# ProPrj__B__2024-10-31.net
KiCad netlist of a schematic drawn in EasyEDA Pro
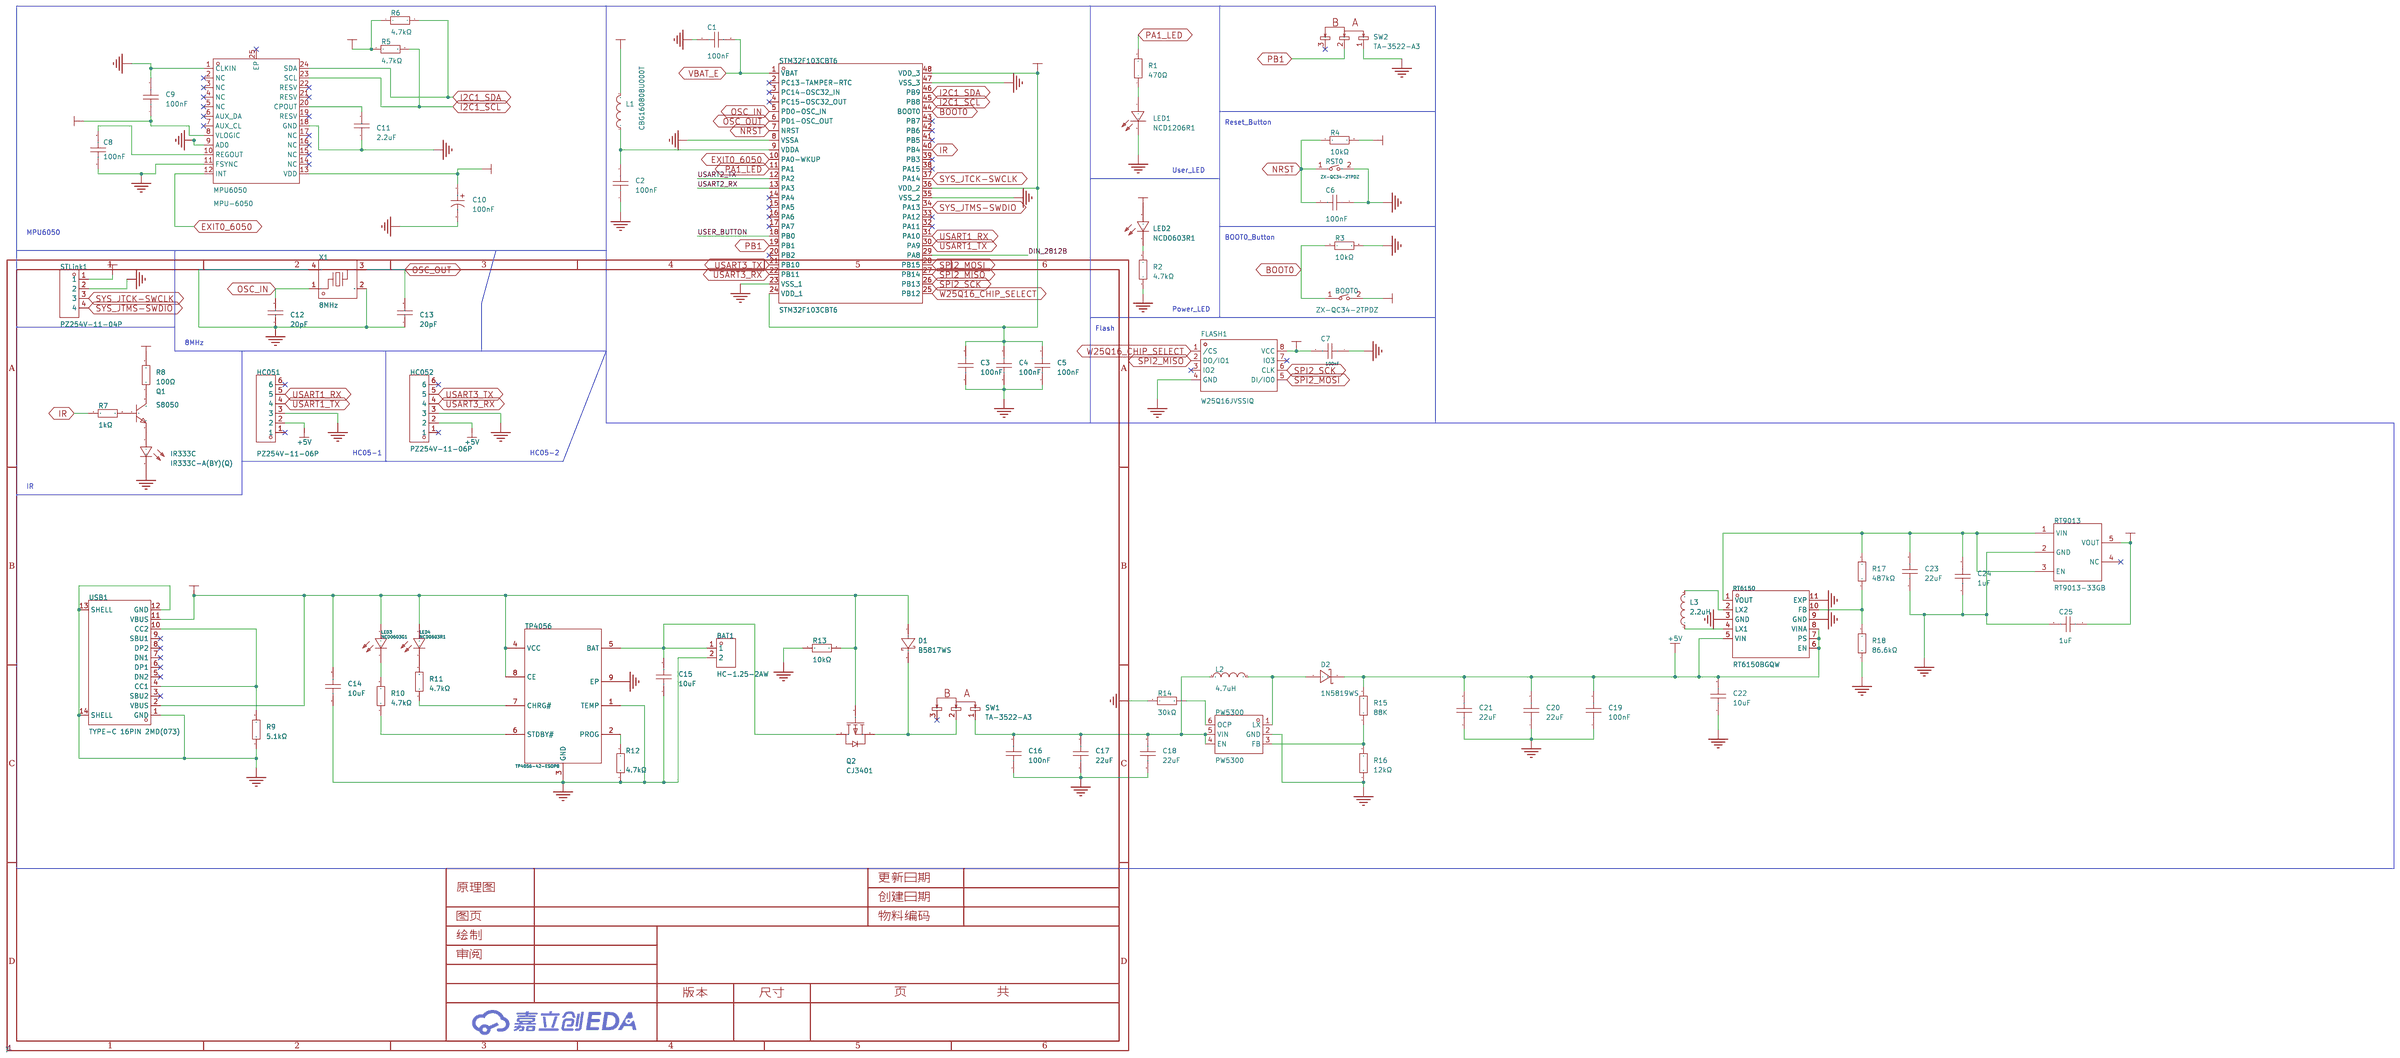
[diagram p0: schematic sheet]

(export (version "E")
  (design (tool "Eeschema 10.0.6"))
  (components
    (comp (ref "BAT1")
      (value "HC-1.25-2AW")
      (footprint "easyedapro:CONN-TH_2P-P1.25_HCTL_HC-1.25-2AW")
      (fields (field (name "Manufacturer") "HCTL(华灿天禄)"))
      (libsource (lib "easyedapro") (part "HC-1.25-2AW"))
    )
    (comp (ref "BOOT0")
      (value "ZX-QC34-2TPDZ")
      (footprint "easyedapro:KEY-SMD_L3.9-W3.0-LS5.0-EH")
      (fields (field (name "Manufacturer") "Megastar(兆星)"))
      (libsource (lib "easyedapro") (part "ZX-QC34-2TPDZ"))
    )
    (comp (ref "C1")
      (value "100nF")
      (footprint "easyedapro:C0603")
      (description "容值:100nF;精度:±10%;额定电压:50V;材质(温度系数):X7R;")
      (fields
        (field (name "Manufacturer Part") "CC0603KRX7R9BB104")
        (field (name "Manufacturer") "YAGEO(国巨)")
      )
      (libsource (lib "easyedapro") (part "CC0603KRX7R9BB104"))
    )
    (comp (ref "C2")
      (value "100nF")
      (footprint "easyedapro:C0603")
      (description "容值:100nF;精度:±10%;额定电压:50V;材质(温度系数):X7R;")
      (fields
        (field (name "Manufacturer Part") "CC0603KRX7R9BB104")
        (field (name "Manufacturer") "YAGEO(国巨)")
      )
      (libsource (lib "easyedapro") (part "CC0603KRX7R9BB104"))
    )
    (comp (ref "C3")
      (value "100nF")
      (footprint "easyedapro:C0603")
      (description "容值:100nF;精度:±10%;额定电压:50V;材质(温度系数):X7R;")
      (fields
        (field (name "Manufacturer Part") "CC0603KRX7R9BB104")
        (field (name "Manufacturer") "YAGEO(国巨)")
      )
      (libsource (lib "easyedapro") (part "CC0603KRX7R9BB104"))
    )
    (comp (ref "C4")
      (value "100nF")
      (footprint "easyedapro:C0603")
      (description "容值:100nF;精度:±10%;额定电压:50V;材质(温度系数):X7R;")
      (fields
        (field (name "Manufacturer Part") "CC0603KRX7R9BB104")
        (field (name "Manufacturer") "YAGEO(国巨)")
      )
      (libsource (lib "easyedapro") (part "CC0603KRX7R9BB104"))
    )
    (comp (ref "C5")
      (value "100nF")
      (footprint "easyedapro:C0603")
      (description "容值:100nF;精度:±10%;额定电压:50V;材质(温度系数):X7R;")
      (fields
        (field (name "Manufacturer Part") "CC0603KRX7R9BB104")
        (field (name "Manufacturer") "YAGEO(国巨)")
      )
      (libsource (lib "easyedapro") (part "CC0603KRX7R9BB104"))
    )
    (comp (ref "C6")
      (value "100nF")
      (footprint "easyedapro:C0603")
      (description "容值:100nF;精度:±10%;额定电压:50V;材质(温度系数):X7R;")
      (fields
        (field (name "Manufacturer Part") "CC0603KRX7R9BB104")
        (field (name "Manufacturer") "YAGEO(国巨)")
      )
      (libsource (lib "easyedapro") (part "CC0603KRX7R9BB104"))
    )
    (comp (ref "C7")
      (value "100nF")
      (footprint "easyedapro:C0603")
      (description "容值:100nF;精度:±10%;额定电压:50V;材质(温度系数):X7R;")
      (fields
        (field (name "Manufacturer Part") "CC0603KRX7R9BB104")
        (field (name "Manufacturer") "YAGEO(国巨)")
      )
      (libsource (lib "easyedapro") (part "CC0603KRX7R9BB104"))
    )
    (comp (ref "C8")
      (value "100nF")
      (footprint "easyedapro:C0603")
      (description "容值:100nF;精度:±10%;额定电压:50V;材质(温度系数):X7R;")
      (fields
        (field (name "Manufacturer Part") "CC0603KRX7R9BB104")
        (field (name "Manufacturer") "YAGEO(国巨)")
      )
      (libsource (lib "easyedapro") (part "CC0603KRX7R9BB104"))
    )
    (comp (ref "C9")
      (value "100nF")
      (footprint "easyedapro:C0603")
      (description "容值:100nF;精度:±10%;额定电压:50V;材质(温度系数):X7R;")
      (fields
        (field (name "Manufacturer Part") "CC0603KRX7R9BB104")
        (field (name "Manufacturer") "YAGEO(国巨)")
      )
      (libsource (lib "easyedapro") (part "CC0603KRX7R9BB104"))
    )
    (comp (ref "C10")
      (value "100nF")
      (footprint "easyedapro:CAP-SMD_L3.2-W1.6-FD")
      (description "容值:100nF;精度:±20%;额定电压:50V;等效串联电阻:20Ω;")
      (fields
        (field (name "Manufacturer Part") "CA45-A-35V-0.1UF-K")
        (field (name "Manufacturer") "CEC(振华新云)")
      )
      (libsource (lib "easyedapro") (part "T491A104M050AT"))
    )
    (comp (ref "C11")
      (value "2.2uF")
      (footprint "easyedapro:C0603")
      (description "容值:2.2uF;精度:±10%;额定电压:16V;材质(温度系数):X5R;")
      (fields
        (field (name "Manufacturer Part") "CL10A225KO8NNNC")
        (field (name "Manufacturer") "SAMSUNG(三星)")
      )
      (libsource (lib "easyedapro") (part "CL10A225KO8NNNC"))
    )
    (comp (ref "C12")
      (value "20pF")
      (footprint "easyedapro:C0603")
      (description "容值:12pF;精度:±5%;额定电压:50V;材质(温度系数):C0G;")
      (fields
        (field (name "Manufacturer Part") "CL10C200JB8NNNC")
        (field (name "Manufacturer") "SAMSUNG(三星)")
      )
      (libsource (lib "easyedapro") (part "CL10C120JB8NNNC"))
    )
    (comp (ref "C13")
      (value "20pF")
      (footprint "easyedapro:C0603")
      (description "容值:12pF;精度:±5%;额定电压:50V;材质(温度系数):C0G;")
      (fields
        (field (name "Manufacturer Part") "CL10C200JB8NNNC")
        (field (name "Manufacturer") "SAMSUNG(三星)")
      )
      (libsource (lib "easyedapro") (part "CL10C120JB8NNNC"))
    )
    (comp (ref "C14")
      (value "10uF")
      (footprint "easyedapro:C0603")
      (description "容值:10uF;精度:±20%;额定电压:16V;材质(温度系数):X5R;")
      (fields
        (field (name "Manufacturer Part") "HGC0603R5106M160NTHJ")
        (field (name "Manufacturer") "Chinocera(华瓷)")
      )
      (libsource (lib "easyedapro") (part "HGC0603R5106M160NTHJ"))
    )
    (comp (ref "C15")
      (value "10uF")
      (footprint "easyedapro:C0603")
      (description "容值:10uF;精度:±20%;额定电压:16V;材质(温度系数):X5R;")
      (fields
        (field (name "Manufacturer Part") "HGC0603R5106M160NTHJ")
        (field (name "Manufacturer") "Chinocera(华瓷)")
      )
      (libsource (lib "easyedapro") (part "HGC0603R5106M160NTHJ"))
    )
    (comp (ref "C16")
      (value "100nF")
      (footprint "easyedapro:C0603")
      (description "容值:100nF;精度:±10%;额定电压:50V;材质(温度系数):X7R;")
      (fields
        (field (name "Manufacturer Part") "CGA0603X7R104K500JT")
        (field (name "Manufacturer") "HRE(芯声)")
      )
      (libsource (lib "easyedapro") (part "cga0603x7r104k500jt"))
    )
    (comp (ref "C17")
      (value "22uF")
      (footprint "easyedapro:C0805")
      (description "容值:22uF;精度:±20%;额定电压:35V;材质(温度系数):X5R;")
      (fields
        (field (name "Manufacturer Part") "CGA0603X5R226M160JT")
        (field (name "Manufacturer") "HRE(芯声)")
      )
      (libsource (lib "easyedapro") (part "CGA0805X5R226M350MT"))
    )
    (comp (ref "C18")
      (value "22uF")
      (footprint "easyedapro:C0805")
      (description "容值:22uF;精度:±20%;额定电压:35V;材质(温度系数):X5R;")
      (fields
        (field (name "Manufacturer Part") "CGA0603X5R226M160JT")
        (field (name "Manufacturer") "HRE(芯声)")
      )
      (libsource (lib "easyedapro") (part "CGA0805X5R226M350MT"))
    )
    (comp (ref "C19")
      (value "100nF")
      (footprint "easyedapro:C0603")
      (description "容值:100nF;精度:±10%;额定电压:50V;材质(温度系数):X7R;")
      (fields
        (field (name "Manufacturer Part") "CGA0603X7R104K500JT")
        (field (name "Manufacturer") "HRE(芯声)")
      )
      (libsource (lib "easyedapro") (part "cga0603x7r104k500jt"))
    )
    (comp (ref "C20")
      (value "22uF")
      (footprint "easyedapro:C0805")
      (description "容值:22uF;精度:±20%;额定电压:35V;材质(温度系数):X5R;")
      (fields
        (field (name "Manufacturer Part") "CGA0603X5R226M160JT")
        (field (name "Manufacturer") "HRE(芯声)")
      )
      (libsource (lib "easyedapro") (part "CGA0805X5R226M350MT"))
    )
    (comp (ref "C21")
      (value "22uF")
      (footprint "easyedapro:C0805")
      (description "容值:22uF;精度:±20%;额定电压:35V;材质(温度系数):X5R;")
      (fields
        (field (name "Manufacturer Part") "CGA0603X5R226M160JT")
        (field (name "Manufacturer") "HRE(芯声)")
      )
      (libsource (lib "easyedapro") (part "CGA0805X5R226M350MT"))
    )
    (comp (ref "C22")
      (value "10uF")
      (footprint "easyedapro:C0603")
      (description "容值:10uF;精度:±20%;额定电压:16V;材质(温度系数):X5R;")
      (fields
        (field (name "Manufacturer Part") "HGC0603R5106M160NTHJ")
        (field (name "Manufacturer") "Chinocera(华瓷)")
      )
      (libsource (lib "easyedapro") (part "HGC0603R5106M160NTHJ"))
    )
    (comp (ref "C23")
      (value "22uF")
      (footprint "easyedapro:C0603")
      (description "容值:22uF;精度:±20%;额定电压:16V;材质(温度系数):X5R;")
      (fields
        (field (name "Manufacturer Part") "CGA0603X5R226M160JT")
        (field (name "Manufacturer") "HRE(芯声)")
      )
      (libsource (lib "easyedapro") (part "CGA0603X5R226M160JT"))
    )
    (comp (ref "C24")
      (value "1uF")
      (footprint "easyedapro:C0603")
      (description "容值:1uF;精度:±10%;额定电压:16V;材质(温度系数):X5R;")
      (fields
        (field (name "Manufacturer Part") "CGA0603X5R105K160JT")
        (field (name "Manufacturer") "HRE(芯声)")
      )
      (libsource (lib "easyedapro") (part "CGA0603X5R105K160JT"))
    )
    (comp (ref "C25")
      (value "1uF")
      (footprint "easyedapro:C0603")
      (description "容值:1uF;精度:±10%;额定电压:16V;材质(温度系数):X5R;")
      (fields
        (field (name "Manufacturer Part") "CGA0603X5R105K160JT")
        (field (name "Manufacturer") "HRE(芯声)")
      )
      (libsource (lib "easyedapro") (part "CGA0603X5R105K160JT"))
    )
    (comp (ref "D1")
      (value "B5817WS")
      (footprint "easyedapro:SOD-323_L1.7-W1.3-LS2.5-FD")
      (description "二极管配置:独立式;正向压降(Vf):450mV@1.0A;直流反向耐压(Vr):20V;平均整流电流(Io):1A;")
      (fields (field (name "Manufacturer") "宏迦橙"))
      (libsource (lib "easyedapro") (part "B5817WS_C7420329"))
    )
    (comp (ref "D2")
      (value "1N5819WS")
      (footprint "easyedapro:SMB_L4.6-W3.6-LS5.3-RD")
      (description "正向压降(Vf):500mV@3A;直流反向耐压(Vr):40V;平均整流电流(Io):3A;")
      (fields (field (name "Manufacturer") "Hottech(合科泰)"))
      (libsource (lib "easyedapro") (part "SS34_C266556"))
    )
    (comp (ref "FLASH1")
      (value "W25Q16JVSSIQ")
      (footprint "easyedapro:SOIC-8_L5.3-W5.3-P1.27-LS8.0-BL")
      (description "（与C82317为同一颗物料，只是编带方式不一样。）3V 16Mbit Serial Flash Memory with dual/quad SPI")
      (fields (field (name "Manufacturer") "WINBOND(华邦)"))
      (libsource (lib "easyedapro") (part "W25Q16JVSSIQTR"))
    )
    (comp (ref "HC051")
      (value "PZ254V-11-06P")
      (footprint "easyedapro:HDR-TH_6P-P2.54-V-M")
      (fields (field (name "Manufacturer") "XFCN(兴飞)"))
      (libsource (lib "easyedapro") (part "PZ254V-11-06P"))
    )
    (comp (ref "HC052")
      (value "PZ254V-11-06P")
      (footprint "easyedapro:HDR-TH_6P-P2.54-V-M")
      (fields (field (name "Manufacturer") "XFCN(兴飞)"))
      (libsource (lib "easyedapro") (part "PZ254V-11-06P"))
    )
    (comp (ref "IR333C")
      (value "IR333C-A(BY)(Q)")
      (footprint "easyedapro:LED-TH_BD5.0-P2.54-FD")
      (description "波长:940nm;")
      (fields (field (name "Manufacturer") "EVERLIGHT(亿光)"))
      (libsource (lib "easyedapro") (part "ir333c-a(by)(q)"))
    )
    (comp (ref "L1")
      (value "CBG160808U000T")
      (footprint "easyedapro:L0603")
      (description "标称阻抗@测试频率:0Ω@100MHz;直流电阻(RDC):100mΩ;")
      (fields (field (name "Manufacturer") "FH(风华)"))
      (libsource (lib "easyedapro") (part "CBG160808U000T"))
    )
    (comp (ref "L2")
      (value "4.7uH")
      (footprint "easyedapro:IND-SMD_L5.4-W5.2_FXL0530")
      (description "电感值:4.7uH;精度:±20%;额定电流:4.5A;饱和电流(Isat):5A;类型:一体成型电感;")
      (fields
        (field (name "Manufacturer Part") "FTC252010S4R7MBCA")
        (field (name "Manufacturer") "cjiang(长江微电)")
      )
      (libsource (lib "easyedapro") (part "FXL0530-4R7-M"))
    )
    (comp (ref "L3")
      (value "2.2uH")
      (footprint "easyedapro:IND-SMD_L2.5-W2.0_MHCHL2520")
      (description "电感值:2.2uH;精度:±20%;额定电流:3A;饱和电流(Isat):3.8A;类型:一体成型电感;")
      (fields
        (field (name "Manufacturer Part") "FTC252012S2R2MBCA")
        (field (name "Manufacturer") "cjiang(长江微电)")
      )
      (libsource (lib "easyedapro") (part "FTC252012S2R2MBCA"))
    )
    (comp (ref "LED1")
      (value "NCD1206R1")
      (footprint "easyedapro:LED1206-R-RD_RED")
      (fields (field (name "Manufacturer") "国星光电"))
      (libsource (lib "easyedapro") (part "FC-3215HRK-620D"))
    )
    (comp (ref "LED2")
      (value "NCD0603R1")
      (footprint "easyedapro:LED0603-RD_RED")
      (fields (field (name "Manufacturer") "国星光电"))
      (libsource (lib "easyedapro") (part "FC-DA1608HRK-620D"))
    )
    (comp (ref "LED3")
      (value "NCD0603G1")
      (footprint "easyedapro:led0603-rd_1")
      (fields (field (name "Manufacturer") "国星光电"))
      (libsource (lib "easyedapro") (part "FC-D1608UGK-520D10"))
    )
    (comp (ref "LED4")
      (value "NCD0603R1")
      (footprint "easyedapro:led0603-rd_1")
      (fields (field (name "Manufacturer") "国星光电"))
      (libsource (lib "easyedapro") (part "FC-D1608UGK-520D10"))
    )
    (comp (ref "MPU6050")
      (value "MPU-6050")
      (footprint "easyedapro:QFN-24_L4.0-W4.0-P0.50-BL-EP2.7")
      (description "传感器类型:加速度计陀螺仪;")
      (fields (field (name "Manufacturer") "TDK InvenSense(应美盛)"))
      (libsource (lib "easyedapro") (part "MPU-6050_C24112"))
    )
    (comp (ref "PW5300")
      (value "PW5300")
      (footprint "easyedapro:SOT-23-6_L2.9-W1.6-P0.95-LS2.8-BL")
      (libsource (lib "easyedapro") (part "PW5300"))
    )
    (comp (ref "Q1")
      (value "S8050")
      (footprint "easyedapro:SOT-23-3_L2.9-W1.6-P1.90-LS2.8-BR")
      (description "晶体管类型:NPN;集电极电流(Ic):500mA;集射极击穿电压(Vceo):25V;功率(Pd):300mW;")
      (fields (field (name "Manufacturer") "Hottech(合科泰)"))
      (libsource (lib "easyedapro") (part "S8050_C181158"))
    )
    (comp (ref "Q2")
      (value "CJ3401")
      (footprint "easyedapro:SOT-23-3_L2.9-W1.6-P1.90-LS2.8-BR")
      (fields (field (name "Manufacturer") "CJ(江苏长电/长晶)"))
      (libsource (lib "easyedapro") (part "CJ3401"))
    )
    (comp (ref "R1")
      (value "470Ω")
      (footprint "easyedapro:R0603")
      (description "电阻类型:厚膜电阻;阻值:470Ω;精度:±1%;功率:100mW;最大工作电压:75V;温度系数:±100ppm/°C;")
      (fields
        (field (name "Manufacturer Part") "0603WAF4700T5E")
        (field (name "Manufacturer") "UNI-ROYAL(厚声)")
      )
      (libsource (lib "easyedapro") (part "0603WAF4700T5E"))
    )
    (comp (ref "R2")
      (value "4.7kΩ")
      (footprint "easyedapro:R0603")
      (description "电阻类型:厚膜电阻;阻值:4.7kΩ;精度:±1%;功率:100mW;最大工作电压:75V;温度系数:±100ppm/°C;")
      (fields
        (field (name "Manufacturer Part") "0603WAF4701T5E")
        (field (name "Manufacturer") "UNI-ROYAL(厚声)")
      )
      (libsource (lib "easyedapro") (part "0603WAF4701T5E"))
    )
    (comp (ref "R3")
      (value "10kΩ")
      (footprint "easyedapro:R0603")
      (description "电阻类型:厚膜电阻;阻值:10kΩ;精度:±1%;功率:100mW;最大工作电压:75V;温度系数:±100ppm/°C;")
      (fields
        (field (name "Manufacturer Part") "0603WAF1002T5E")
        (field (name "Manufacturer") "UNI-ROYAL(厚声)")
      )
      (libsource (lib "easyedapro") (part "0603WAF1002T5E"))
    )
    (comp (ref "R4")
      (value "10kΩ")
      (footprint "easyedapro:R0603")
      (description "电阻类型:厚膜电阻;阻值:10kΩ;精度:±1%;功率:100mW;最大工作电压:75V;温度系数:±100ppm/°C;")
      (fields
        (field (name "Manufacturer Part") "0603WAF1002T5E")
        (field (name "Manufacturer") "UNI-ROYAL(厚声)")
      )
      (libsource (lib "easyedapro") (part "0603WAF1002T5E"))
    )
    (comp (ref "R5")
      (value "4.7kΩ")
      (footprint "easyedapro:R0603")
      (description "电阻类型:厚膜电阻;阻值:4.7kΩ;精度:±1%;功率:100mW;最大工作电压:75V;温度系数:±100ppm/°C;")
      (fields
        (field (name "Manufacturer Part") "0603WAF4701T5E")
        (field (name "Manufacturer") "UNI-ROYAL(厚声)")
      )
      (libsource (lib "easyedapro") (part "0603WAF4701T5E"))
    )
    (comp (ref "R6")
      (value "4.7kΩ")
      (footprint "easyedapro:R0603")
      (description "电阻类型:厚膜电阻;阻值:4.7kΩ;精度:±1%;功率:100mW;最大工作电压:75V;温度系数:±100ppm/°C;")
      (fields
        (field (name "Manufacturer Part") "0603WAF4701T5E")
        (field (name "Manufacturer") "UNI-ROYAL(厚声)")
      )
      (libsource (lib "easyedapro") (part "0603WAF4701T5E"))
    )
    (comp (ref "R7")
      (value "1kΩ")
      (footprint "easyedapro:R0603")
      (description "电阻类型:厚膜电阻;阻值:1kΩ;精度:±1%;功率:100mW;最大工作电压:75V;温度系数:±100ppm/°C;")
      (fields
        (field (name "Manufacturer Part") "0603WAF1001T5E")
        (field (name "Manufacturer") "UNI-ROYAL(厚声)")
      )
      (libsource (lib "easyedapro") (part "0603WAF1001T5E"))
    )
    (comp (ref "R8")
      (value "100Ω")
      (footprint "easyedapro:R0603")
      (description "电阻类型:厚膜电阻;阻值:100Ω;精度:±1%;功率:100mW;最大工作电压:75V;温度系数:±200ppm/°C;")
      (fields
        (field (name "Manufacturer Part") "0603WAF1000T5E")
        (field (name "Manufacturer") "UNI-ROYAL(厚声)")
      )
      (libsource (lib "easyedapro") (part "0603WAF1000T5E"))
    )
    (comp (ref "R9")
      (value "5.1kΩ")
      (footprint "easyedapro:R0603")
      (description "电阻类型:厚膜电阻;阻值:5.1kΩ;精度:±1%;功率:100mW;最大工作电压:75V;温度系数:±100ppm/°C;")
      (fields
        (field (name "Manufacturer Part") "0603WAF5101T5E")
        (field (name "Manufacturer") "UNI-ROYAL(厚声)")
      )
      (libsource (lib "easyedapro") (part "0603WAF5101T5E"))
    )
    (comp (ref "R10")
      (value "4.7kΩ")
      (footprint "easyedapro:R0603")
      (description "电阻类型:厚膜电阻;阻值:4.7kΩ;精度:±1%;功率:100mW;最大工作电压:75V;温度系数:±100ppm/°C;")
      (fields
        (field (name "Manufacturer Part") "0603WAF4701T5E")
        (field (name "Manufacturer") "UNI-ROYAL(厚声)")
      )
      (libsource (lib "easyedapro") (part "0603WAF4701T5E"))
    )
    (comp (ref "R11")
      (value "4.7kΩ")
      (footprint "easyedapro:R0603")
      (description "电阻类型:厚膜电阻;阻值:4.7kΩ;精度:±1%;功率:100mW;最大工作电压:75V;温度系数:±100ppm/°C;")
      (fields
        (field (name "Manufacturer Part") "0603WAF4701T5E")
        (field (name "Manufacturer") "UNI-ROYAL(厚声)")
      )
      (libsource (lib "easyedapro") (part "0603WAF4701T5E"))
    )
    (comp (ref "R12")
      (value "4.7kΩ")
      (footprint "easyedapro:R0603")
      (description "电阻类型:厚膜电阻;阻值:4.7kΩ;精度:±1%;功率:100mW;最大工作电压:75V;温度系数:±100ppm/°C;")
      (fields
        (field (name "Manufacturer Part") "0603WAF4701T5E")
        (field (name "Manufacturer") "UNI-ROYAL(厚声)")
      )
      (libsource (lib "easyedapro") (part "0603WAF4701T5E"))
    )
    (comp (ref "R13")
      (value "10kΩ")
      (footprint "easyedapro:R0603")
      (description "电阻类型:厚膜电阻;阻值:10kΩ;精度:±1%;功率:100mW;最大工作电压:75V;温度系数:±100ppm/°C;")
      (fields
        (field (name "Manufacturer Part") "0603WAF1002T5E")
        (field (name "Manufacturer") "UNI-ROYAL(厚声)")
      )
      (libsource (lib "easyedapro") (part "0603WAF1002T5E"))
    )
    (comp (ref "R14")
      (value "30kΩ")
      (footprint "easyedapro:R0603")
      (description "电阻类型:厚膜电阻;阻值:30kΩ;精度:±1%;功率:100mW;最大工作电压:75V;温度系数:±100ppm/°C;")
      (fields
        (field (name "Manufacturer Part") "0603WAF3002T5E")
        (field (name "Manufacturer") "UNI-ROYAL(厚声)")
      )
      (libsource (lib "easyedapro") (part "0603WAF3002T5E"))
    )
    (comp (ref "R15")
      (value "88K")
      (footprint "easyedapro:R0603")
      (fields
        (field (name "Manufacturer Part") "RCT0388K7FLF")
        (field (name "Manufacturer") "HKR(香港电阻)")
        (field (name "Tolerance") "±1%")
      )
      (libsource (lib "easyedapro") (part "电阻"))
    )
    (comp (ref "R16")
      (value "12kΩ")
      (footprint "easyedapro:R0603")
      (description "电阻类型:厚膜电阻;阻值:12kΩ;精度:±1%;功率:100mW;最大工作电压:75V;温度系数:±100ppm/°C;")
      (fields
        (field (name "Manufacturer Part") "0603WAF1202T5E")
        (field (name "Manufacturer") "UNI-ROYAL(厚声)")
      )
      (libsource (lib "easyedapro") (part "0603WAF1202T5E"))
    )
    (comp (ref "R17")
      (value "487kΩ")
      (footprint "easyedapro:R0603")
      (description "电阻类型:厚膜电阻;阻值:487kΩ;精度:±1%;功率:100mW;最大工作电压:75V;温度系数:±100ppm/°C;")
      (fields
        (field (name "Manufacturer Part") "0603WAF4873T5E")
        (field (name "Manufacturer") "UNI-ROYAL(厚声)")
      )
      (libsource (lib "easyedapro") (part "0603WAF4873T5E"))
    )
    (comp (ref "R18")
      (value "86.6kΩ")
      (footprint "easyedapro:R0603")
      (description "电阻类型:厚膜电阻;阻值:86.6kΩ;精度:±1%;功率:100mW;最大工作电压:75V;温度系数:±100ppm/°C;")
      (fields
        (field (name "Manufacturer Part") "0603WAF8662T5E")
        (field (name "Manufacturer") "UNI-ROYAL(厚声)")
      )
      (libsource (lib "easyedapro") (part "0603WAF8662T5E"))
    )
    (comp (ref "RST0")
      (value "ZX-QC34-2TPDZ")
      (footprint "easyedapro:KEY-SMD_L3.9-W3.0-LS5.0-EH")
      (fields (field (name "Manufacturer") "Megastar(兆星)"))
      (libsource (lib "easyedapro") (part "ZX-QC34-2TPDZ"))
    )
    (comp (ref "RT6150")
      (value "RT6150BGQW")
      (footprint "easyedapro:WSON-10_L2.5-W2.5-P0.50-BL-EP")
      (description "功能类型:升降压型;输入电压:1.8V~5.5V;输出电压:1.8V~5.5V;输出电流(最大值):800mA;")
      (fields (field (name "Manufacturer") "RICHTEK(立锜)"))
      (libsource (lib "easyedapro") (part "RT6150BGQW"))
    )
    (comp (ref "RT9013")
      (value "RT9013-33GB")
      (footprint "easyedapro:SOT-23-5_L3.0-W1.7-P0.95-LS2.8-BL")
      (description "输出类型:固定;最大输入电压:5.5V;输出电压:3.3V;最大输出电流:500mA;电源纹波抑制比(PSRR):50dB@(10kHz);输出极性:正极;")
      (fields (field (name "Manufacturer") "RICHTEK(立锜)"))
      (libsource (lib "easyedapro") (part "RT9013-33GB"))
    )
    (comp (ref "STLink1")
      (value "PZ254V-11-04P")
      (footprint "easyedapro:HDR-TH_4P-P2.54-V-M")
      (fields (field (name "Manufacturer") "XFCN(兴飞)"))
      (libsource (lib "easyedapro") (part "PZ254V-11-04P_C2691448"))
    )
    (comp (ref "STM32F103CBT6")
      (value "STM32F103CBT6")
      (fields (field (name "Manufacturer") "ST(意法半导体)"))
      (libsource (lib "easyedapro") (part "APM32F103CBT6"))
    )
    (comp (ref "SW1")
      (value "TA-3522-A3")
      (footprint "easyedapro:SW-TH_3P-L9.1-W3.5-P2.50-A3")
      (fields (field (name "Manufacturer") "Yuandi(元迪)"))
      (libsource (lib "easyedapro") (part "TA-3522-A3"))
    )
    (comp (ref "SW2")
      (value "TA-3522-A3")
      (footprint "easyedapro:SW-TH_3P-L9.1-W3.5-P2.50-A3")
      (fields (field (name "Manufacturer") "Yuandi(元迪)"))
      (libsource (lib "easyedapro") (part "TA-3522-A3"))
    )
    (comp (ref "TP4056")
      (value "TP4056-42-ESOP8")
      (footprint "easyedapro:ESOP-8_L4.9-W3.9-P1.27-LS6.0-BL-EP")
      (description "锂电池充电芯片 42代表电池满电电压4.2V。")
      (fields (field (name "Manufacturer") "TOPPOWER(南京拓微)"))
      (libsource (lib "easyedapro") (part "TP4056"))
    )
    (comp (ref "USB1")
      (value "TYPE-C 16PIN 2MD(073)")
      (footprint "easyedapro:USB-C-SMD_TYPE-C-6PIN-2MD-073")
      (description "连接器类型:Type-C;标准:USB 3.1;公母:母;安装方式:卧贴;触点数量:16P;端口数量:1;额定电流 - 电源:5A;工作温度范围:-25°C~+85°C;")
      (fields (field (name "Manufacturer") "SHOU HAN(首韩)"))
      (libsource (lib "easyedapro") (part "TYPE-C 16PIN 2MD(073)"))
    )
    (comp (ref "X1")
      (value "8MHz")
      (footprint "easyedapro:OSC-SMD_4P-L3.2-W2.5-BL")
      (description "晶振类型:贴片晶振;频率:8MHz;常温频差:±10ppm;外接负载电容:12pF;频率稳定度(全温):±20ppm;")
      (fields (field (name "Manufacturer Part") "X32258MOB4SI") (field (name "Manufacturer") "YXC(扬兴晶振)"))
      (libsource (lib "easyedapro") (part "x32258mob4si"))
    )
  )
  (nets
    (net (code "1") (name "+5V") (class "Default")
      (node (ref "C19") (pin "2") (pinfunction "2_2") (pintype "unspecified"))
      (node (ref "C20") (pin "2") (pinfunction "2_2") (pintype "unspecified"))
      (node (ref "C21") (pin "2") (pinfunction "2_2") (pintype "unspecified"))
      (node (ref "C22") (pin "2") (pinfunction "2_2") (pintype "unspecified"))
      (node (ref "D2") (pin "1") (pinfunction "C_1") (pintype "unspecified"))
      (node (ref "HC051") (pin "2") (pinfunction "2_2") (pintype "unspecified"))
      (node (ref "HC052") (pin "2") (pinfunction "2_2") (pintype "unspecified"))
      (node (ref "R15") (pin "2") (pinfunction "2_2") (pintype "input"))
      (node (ref "RT6150") (pin "5") (pinfunction "VIN_5") (pintype "input"))
      (node (ref "RT6150") (pin "6") (pinfunction "EN_6") (pintype "input"))
      (node (ref "RT6150") (pin "7") (pinfunction "PS_7") (pintype "input"))
      (node (ref "RT6150") (pin "8") (pinfunction "VINA_8") (pintype "input"))
    )
    (net (code "2") (name "/DIN_2812B") (class "Default")
      (node (ref "STM32F103CBT6") (pin "29") (pinfunction "PA8_29") (pintype "unspecified"))
    )
    (net (code "3") (name "/USART2_RX") (class "Default")
      (node (ref "STM32F103CBT6") (pin "13") (pinfunction "PA3_13") (pintype "unspecified"))
    )
    (net (code "4") (name "/USART2_TX") (class "Default")
      (node (ref "STM32F103CBT6") (pin "12") (pinfunction "PA2_12") (pintype "unspecified"))
    )
    (net (code "5") (name "/USER_BUTTON") (class "Default")
      (node (ref "STM32F103CBT6") (pin "18") (pinfunction "PB0_18") (pintype "unspecified"))
    )
    (net (code "6") (name "3V3") (class "Default")
      (node (ref "BOOT0") (pin "2") (pinfunction "2_2") (pintype "unspecified"))
      (node (ref "C10") (pin "1") (pinfunction "1_1") (pintype "input"))
      (node (ref "C25") (pin "1") (pinfunction "1_1") (pintype "unspecified"))
      (node (ref "C3") (pin "2") (pinfunction "2_2") (pintype "unspecified"))
      (node (ref "C4") (pin "2") (pinfunction "2_2") (pintype "unspecified"))
      (node (ref "C5") (pin "2") (pinfunction "2_2") (pintype "unspecified"))
      (node (ref "C7") (pin "2") (pinfunction "2_2") (pintype "unspecified"))
      (node (ref "C9") (pin "1") (pinfunction "1_1") (pintype "unspecified"))
      (node (ref "FLASH1") (pin "8") (pinfunction "VCC_8") (pintype "unspecified"))
      (node (ref "L1") (pin "2") (pinfunction "2_2") (pintype "unspecified"))
      (node (ref "LED2") (pin "2") (pinfunction "A_2") (pintype "input"))
      (node (ref "MPU6050") (pin "13") (pinfunction "VDD_13") (pintype "unspecified"))
      (node (ref "MPU6050") (pin "8") (pinfunction "VLOGIC_8") (pintype "unspecified"))
      (node (ref "R4") (pin "2") (pinfunction "2_2") (pintype "input"))
      (node (ref "R5") (pin "1") (pinfunction "1_1") (pintype "input"))
      (node (ref "R6") (pin "1") (pinfunction "1_1") (pintype "input"))
      (node (ref "R8") (pin "2") (pinfunction "2_2") (pintype "input"))
      (node (ref "RT9013") (pin "5") (pinfunction "VOUT_5") (pintype "unspecified"))
      (node (ref "STLink1") (pin "1") (pinfunction "1_1") (pintype "unspecified"))
      (node (ref "STM32F103CBT6") (pin "24") (pinfunction "VDD_1_24") (pintype "unspecified"))
      (node (ref "STM32F103CBT6") (pin "36") (pinfunction "VDD_2_36") (pintype "unspecified"))
      (node (ref "STM32F103CBT6") (pin "48") (pinfunction "VDD_3_48") (pintype "unspecified"))
    )
    (net (code "7") (name "BOOT0") (class "Default")
      (node (ref "BOOT0") (pin "1") (pinfunction "1_1") (pintype "unspecified"))
      (node (ref "R3") (pin "1") (pinfunction "1_1") (pintype "input"))
      (node (ref "STM32F103CBT6") (pin "44") (pinfunction "BOOT0_44") (pintype "unspecified"))
    )
    (net (code "8") (name "EXIT0_6050") (class "Default")
      (node (ref "MPU6050") (pin "12") (pinfunction "INT_12") (pintype "unspecified"))
      (node (ref "STM32F103CBT6") (pin "10") (pinfunction "PA0-WKUP_10") (pintype "unspecified"))
    )
    (net (code "9") (name "GND") (class "Default")
      (node (ref "BAT1") (pin "2") (pinfunction "2_2") (pintype "unspecified"))
      (node (ref "C1") (pin "1") (pinfunction "1_1") (pintype "unspecified"))
      (node (ref "C10") (pin "2") (pinfunction "2_2") (pintype "input"))
      (node (ref "C11") (pin "1") (pinfunction "1_1") (pintype "input"))
      (node (ref "C12") (pin "1") (pinfunction "1_1") (pintype "input"))
      (node (ref "C13") (pin "1") (pinfunction "1_1") (pintype "input"))
      (node (ref "C14") (pin "1") (pinfunction "1_1") (pintype "unspecified"))
      (node (ref "C15") (pin "1") (pinfunction "1_1") (pintype "unspecified"))
      (node (ref "C16") (pin "1") (pinfunction "1_1") (pintype "unspecified"))
      (node (ref "C17") (pin "1") (pinfunction "1_1") (pintype "unspecified"))
      (node (ref "C18") (pin "1") (pinfunction "1_1") (pintype "unspecified"))
      (node (ref "C19") (pin "1") (pinfunction "1_1") (pintype "unspecified"))
      (node (ref "C2") (pin "1") (pinfunction "1_1") (pintype "unspecified"))
      (node (ref "C20") (pin "1") (pinfunction "1_1") (pintype "unspecified"))
      (node (ref "C21") (pin "1") (pinfunction "1_1") (pintype "unspecified"))
      (node (ref "C22") (pin "1") (pinfunction "1_1") (pintype "unspecified"))
      (node (ref "C23") (pin "1") (pinfunction "1_1") (pintype "unspecified"))
      (node (ref "C24") (pin "1") (pinfunction "1_1") (pintype "unspecified"))
      (node (ref "C25") (pin "2") (pinfunction "2_2") (pintype "unspecified"))
      (node (ref "C3") (pin "1") (pinfunction "1_1") (pintype "unspecified"))
      (node (ref "C4") (pin "1") (pinfunction "1_1") (pintype "unspecified"))
      (node (ref "C5") (pin "1") (pinfunction "1_1") (pintype "unspecified"))
      (node (ref "C6") (pin "1") (pinfunction "1_1") (pintype "unspecified"))
      (node (ref "C7") (pin "1") (pinfunction "1_1") (pintype "unspecified"))
      (node (ref "C8") (pin "1") (pinfunction "1_1") (pintype "unspecified"))
      (node (ref "C9") (pin "2") (pinfunction "2_2") (pintype "unspecified"))
      (node (ref "FLASH1") (pin "4") (pinfunction "GND_4") (pintype "unspecified"))
      (node (ref "HC051") (pin "3") (pinfunction "3_3") (pintype "unspecified"))
      (node (ref "HC052") (pin "3") (pinfunction "3_3") (pintype "unspecified"))
      (node (ref "IR333C") (pin "2") (pinfunction "C_2") (pintype "input"))
      (node (ref "LED1") (pin "2") (pinfunction "K_2") (pintype "unspecified"))
      (node (ref "MPU6050") (pin "1") (pinfunction "CLKIN_1") (pintype "unspecified"))
      (node (ref "MPU6050") (pin "11") (pinfunction "FSYNC_11") (pintype "unspecified"))
      (node (ref "MPU6050") (pin "18") (pinfunction "GND_18") (pintype "unspecified"))
      (node (ref "MPU6050") (pin "9") (pinfunction "AD0_9") (pintype "unspecified"))
      (node (ref "PW5300") (pin "2") (pinfunction "GND_2") (pintype "unspecified"))
      (node (ref "R12") (pin "1") (pinfunction "1_1") (pintype "input"))
      (node (ref "R13") (pin "1") (pinfunction "1_1") (pintype "input"))
      (node (ref "R14") (pin "1") (pinfunction "1_1") (pintype "input"))
      (node (ref "R16") (pin "1") (pinfunction "1_1") (pintype "input"))
      (node (ref "R18") (pin "1") (pinfunction "1_1") (pintype "input"))
      (node (ref "R2") (pin "1") (pinfunction "1_1") (pintype "input"))
      (node (ref "R3") (pin "2") (pinfunction "2_2") (pintype "input"))
      (node (ref "R9") (pin "1") (pinfunction "1_1") (pintype "input"))
      (node (ref "RST0") (pin "2") (pinfunction "2_2") (pintype "unspecified"))
      (node (ref "RT6150") (pin "11") (pinfunction "EXP_11") (pintype "input"))
      (node (ref "RT6150") (pin "3") (pinfunction "GND_3") (pintype "input"))
      (node (ref "RT6150") (pin "9") (pinfunction "GND_9") (pintype "input"))
      (node (ref "RT9013") (pin "2") (pinfunction "GND_2") (pintype "unspecified"))
      (node (ref "STLink1") (pin "2") (pinfunction "2_2") (pintype "unspecified"))
      (node (ref "STM32F103CBT6") (pin "23") (pinfunction "VSS_1_23") (pintype "unspecified"))
      (node (ref "STM32F103CBT6") (pin "35") (pinfunction "VSS_2_35") (pintype "unspecified"))
      (node (ref "STM32F103CBT6") (pin "47") (pinfunction "VSS_3_47") (pintype "unspecified"))
      (node (ref "STM32F103CBT6") (pin "8") (pinfunction "VSSA_8") (pintype "unspecified"))
      (node (ref "SW2") (pin "1") (pinfunction "1_1") (pintype "unspecified"))
      (node (ref "TP4056") (pin "1") (pinfunction "TEMP_1") (pintype "unspecified"))
      (node (ref "TP4056") (pin "3") (pinfunction "GND_3") (pintype "unspecified"))
      (node (ref "TP4056") (pin "9") (pinfunction "EP_9") (pintype "unspecified"))
      (node (ref "USB1") (pin "1") (pinfunction "GND_1") (pintype "unspecified"))
      (node (ref "USB1") (pin "12") (pinfunction "GND_12") (pintype "unspecified"))
      (node (ref "USB1") (pin "13") (pinfunction "SHELL_13") (pintype "unspecified"))
      (node (ref "USB1") (pin "14") (pinfunction "SHELL_14") (pintype "unspecified"))
      (node (ref "X1") (pin "2") (pinfunction "GND_2") (pintype "input"))
      (node (ref "X1") (pin "4") (pinfunction "GND_4") (pintype "input"))
    )
    (net (code "10") (name "I2C1_SCL") (class "Default")
      (node (ref "MPU6050") (pin "23") (pinfunction "SCL_23") (pintype "unspecified"))
      (node (ref "R5") (pin "2") (pinfunction "2_2") (pintype "input"))
      (node (ref "STM32F103CBT6") (pin "45") (pinfunction "PB8_45") (pintype "unspecified"))
    )
    (net (code "11") (name "I2C1_SDA") (class "Default")
      (node (ref "MPU6050") (pin "24") (pinfunction "SDA_24") (pintype "unspecified"))
      (node (ref "R6") (pin "2") (pinfunction "2_2") (pintype "input"))
      (node (ref "STM32F103CBT6") (pin "46") (pinfunction "PB9_46") (pintype "unspecified"))
    )
    (net (code "12") (name "IR") (class "Default")
      (node (ref "R7") (pin "1") (pinfunction "1_1") (pintype "input"))
      (node (ref "STM32F103CBT6") (pin "40") (pinfunction "PB4_40") (pintype "unspecified"))
    )
    (net (code "13") (name "NRST") (class "Default")
      (node (ref "C6") (pin "2") (pinfunction "2_2") (pintype "unspecified"))
      (node (ref "R4") (pin "1") (pinfunction "1_1") (pintype "input"))
      (node (ref "RST0") (pin "1") (pinfunction "1_1") (pintype "unspecified"))
      (node (ref "STM32F103CBT6") (pin "7") (pinfunction "NRST_7") (pintype "unspecified"))
    )
    (net (code "14") (name "Net-(D1-K)") (class "Default")
      (node (ref "D1") (pin "2") (pinfunction "K_2") (pintype "unspecified"))
      (node (ref "Q2") (pin "2") (pinfunction "S_2") (pintype "unspecified"))
      (node (ref "SW1") (pin "2") (pinfunction "2_2") (pintype "unspecified"))
    )
    (net (code "15") (name "Net-(D2-A)") (class "Default")
      (node (ref "D2") (pin "2") (pinfunction "A_2") (pintype "unspecified"))
      (node (ref "L2") (pin "2") (pinfunction "2_2") (pintype "unspecified"))
      (node (ref "PW5300") (pin "1") (pinfunction "LX_1") (pintype "unspecified"))
    )
    (net (code "16") (name "Net-(IR333C-A)") (class "Default")
      (node (ref "IR333C") (pin "1") (pinfunction "A_1") (pintype "input"))
      (node (ref "Q1") (pin "2") (pinfunction "2_2") (pintype "input"))
    )
    (net (code "17") (name "Net-(LED1-A)") (class "Default")
      (node (ref "LED1") (pin "1") (pinfunction "A_1") (pintype "unspecified"))
      (node (ref "R1") (pin "1") (pinfunction "1_1") (pintype "input"))
    )
    (net (code "18") (name "Net-(LED2-K)") (class "Default")
      (node (ref "LED2") (pin "1") (pinfunction "K_1") (pintype "input"))
      (node (ref "R2") (pin "2") (pinfunction "2_2") (pintype "input"))
    )
    (net (code "19") (name "Net-(LED3-K)") (class "Default")
      (node (ref "LED3") (pin "1") (pinfunction "K_1") (pintype "input"))
      (node (ref "R10") (pin "2") (pinfunction "2_2") (pintype "input"))
    )
    (net (code "20") (name "Net-(LED4-K)") (class "Default")
      (node (ref "LED4") (pin "1") (pinfunction "K_1") (pintype "input"))
      (node (ref "R11") (pin "2") (pinfunction "2_2") (pintype "input"))
    )
    (net (code "21") (name "Net-(MPU6050-CPOUT)") (class "Default")
      (node (ref "C11") (pin "2") (pinfunction "2_2") (pintype "input"))
      (node (ref "MPU6050") (pin "20") (pinfunction "CPOUT_20") (pintype "unspecified"))
    )
    (net (code "22") (name "Net-(MPU6050-REGOUT)") (class "Default")
      (node (ref "C8") (pin "2") (pinfunction "2_2") (pintype "unspecified"))
      (node (ref "MPU6050") (pin "10") (pinfunction "REGOUT_10") (pintype "unspecified"))
    )
    (net (code "23") (name "Net-(PW5300-EN)") (class "Default")
      (node (ref "C16") (pin "2") (pinfunction "2_2") (pintype "unspecified"))
      (node (ref "C17") (pin "2") (pinfunction "2_2") (pintype "unspecified"))
      (node (ref "C18") (pin "2") (pinfunction "2_2") (pintype "unspecified"))
      (node (ref "L2") (pin "1") (pinfunction "1_1") (pintype "unspecified"))
      (node (ref "PW5300") (pin "4") (pinfunction "EN_4") (pintype "unspecified"))
      (node (ref "PW5300") (pin "5") (pinfunction "VIN_5") (pintype "unspecified"))
      (node (ref "SW1") (pin "1") (pinfunction "1_1") (pintype "unspecified"))
    )
    (net (code "24") (name "Net-(PW5300-FB)") (class "Default")
      (node (ref "PW5300") (pin "3") (pinfunction "FB_3") (pintype "unspecified"))
      (node (ref "R15") (pin "1") (pinfunction "1_1") (pintype "input"))
      (node (ref "R16") (pin "2") (pinfunction "2_2") (pintype "input"))
    )
    (net (code "25") (name "Net-(PW5300-OCP)") (class "Default")
      (node (ref "PW5300") (pin "6") (pinfunction "OCP_6") (pintype "unspecified"))
      (node (ref "R14") (pin "2") (pinfunction "2_2") (pintype "input"))
    )
    (net (code "26") (name "Net-(Q1-Pad1)") (class "Default")
      (node (ref "Q1") (pin "1") (pinfunction "1_1") (pintype "input"))
      (node (ref "R7") (pin "2") (pinfunction "2_2") (pintype "input"))
    )
    (net (code "27") (name "Net-(Q1-Pad3)") (class "Default")
      (node (ref "Q1") (pin "3") (pinfunction "3_3") (pintype "input"))
      (node (ref "R8") (pin "1") (pinfunction "1_1") (pintype "input"))
    )
    (net (code "28") (name "Net-(Q2-D)") (class "Default")
      (node (ref "BAT1") (pin "1") (pinfunction "1_1") (pintype "unspecified"))
      (node (ref "C15") (pin "2") (pinfunction "2_2") (pintype "unspecified"))
      (node (ref "Q2") (pin "3") (pinfunction "D_3") (pintype "unspecified"))
      (node (ref "TP4056") (pin "5") (pinfunction "BAT_5") (pintype "unspecified"))
    )
    (net (code "29") (name "Net-(RT6150-FB)") (class "Default")
      (node (ref "R17") (pin "1") (pinfunction "1_1") (pintype "input"))
      (node (ref "R18") (pin "2") (pinfunction "2_2") (pintype "input"))
      (node (ref "RT6150") (pin "10") (pinfunction "FB_10") (pintype "input"))
    )
    (net (code "30") (name "Net-(RT6150-LX1)") (class "Default")
      (node (ref "L3") (pin "1") (pinfunction "1_1") (pintype "unspecified"))
      (node (ref "RT6150") (pin "4") (pinfunction "LX1_4") (pintype "input"))
    )
    (net (code "31") (name "Net-(RT6150-LX2)") (class "Default")
      (node (ref "L3") (pin "2") (pinfunction "2_2") (pintype "unspecified"))
      (node (ref "RT6150") (pin "2") (pinfunction "LX2_2") (pintype "input"))
    )
    (net (code "32") (name "Net-(RT6150-VOUT)") (class "Default")
      (node (ref "C23") (pin "2") (pinfunction "2_2") (pintype "unspecified"))
      (node (ref "C24") (pin "2") (pinfunction "2_2") (pintype "unspecified"))
      (node (ref "R17") (pin "2") (pinfunction "2_2") (pintype "input"))
      (node (ref "RT6150") (pin "1") (pinfunction "VOUT_1") (pintype "input"))
      (node (ref "RT9013") (pin "1") (pinfunction "VIN_1") (pintype "unspecified"))
      (node (ref "RT9013") (pin "3") (pinfunction "EN_3") (pintype "unspecified"))
    )
    (net (code "33") (name "Net-(STM32F103CBT6-VDDA)") (class "Default")
      (node (ref "C2") (pin "2") (pinfunction "2_2") (pintype "unspecified"))
      (node (ref "L1") (pin "1") (pinfunction "1_1") (pintype "unspecified"))
      (node (ref "STM32F103CBT6") (pin "9") (pinfunction "VDDA_9") (pintype "unspecified"))
    )
    (net (code "34") (name "Net-(TP4056-CHRG#)") (class "Default")
      (node (ref "R11") (pin "1") (pinfunction "1_1") (pintype "input"))
      (node (ref "TP4056") (pin "7") (pinfunction "CHRG#_7") (pintype "unspecified"))
    )
    (net (code "35") (name "Net-(TP4056-PROG)") (class "Default")
      (node (ref "R12") (pin "2") (pinfunction "2_2") (pintype "input"))
      (node (ref "TP4056") (pin "2") (pinfunction "PROG_2") (pintype "unspecified"))
    )
    (net (code "36") (name "Net-(TP4056-STDBY#)") (class "Default")
      (node (ref "R10") (pin "1") (pinfunction "1_1") (pintype "input"))
      (node (ref "TP4056") (pin "6") (pinfunction "STDBY#_6") (pintype "unspecified"))
    )
    (net (code "37") (name "Net-(USB1-CC1)") (class "Default")
      (node (ref "R9") (pin "2") (pinfunction "2_2") (pintype "input"))
      (node (ref "USB1") (pin "10") (pinfunction "CC2_10") (pintype "unspecified"))
      (node (ref "USB1") (pin "4") (pinfunction "CC1_4") (pintype "unspecified"))
    )
    (net (code "38") (name "OSC_IN") (class "Default")
      (node (ref "C12") (pin "2") (pinfunction "2_2") (pintype "input"))
      (node (ref "STM32F103CBT6") (pin "5") (pinfunction "PD0-OSC_IN_5") (pintype "unspecified"))
      (node (ref "X1") (pin "1") (pinfunction "1_1") (pintype "input"))
    )
    (net (code "39") (name "OSC_OUT") (class "Default")
      (node (ref "C13") (pin "2") (pinfunction "2_2") (pintype "input"))
      (node (ref "STM32F103CBT6") (pin "6") (pinfunction "PD1-OSC_OUT_6") (pintype "unspecified"))
      (node (ref "X1") (pin "3") (pinfunction "3_3") (pintype "input"))
    )
    (net (code "40") (name "PA1_LED") (class "Default")
      (node (ref "R1") (pin "2") (pinfunction "2_2") (pintype "input"))
      (node (ref "STM32F103CBT6") (pin "11") (pinfunction "PA1_11") (pintype "unspecified"))
    )
    (net (code "41") (name "PB1") (class "Default")
      (node (ref "STM32F103CBT6") (pin "19") (pinfunction "PB1_19") (pintype "unspecified"))
      (node (ref "SW2") (pin "2") (pinfunction "2_2") (pintype "unspecified"))
    )
    (net (code "42") (name "SPI2_MISO") (class "Default")
      (node (ref "FLASH1") (pin "2") (pinfunction "DO/IO1_2") (pintype "unspecified"))
      (node (ref "STM32F103CBT6") (pin "27") (pinfunction "PB14_27") (pintype "unspecified"))
    )
    (net (code "43") (name "SPI2_MOSI") (class "Default")
      (node (ref "FLASH1") (pin "5") (pinfunction "DI/IO0_5") (pintype "unspecified"))
      (node (ref "STM32F103CBT6") (pin "28") (pinfunction "PB15_28") (pintype "unspecified"))
    )
    (net (code "44") (name "SPI2_SCK") (class "Default")
      (node (ref "FLASH1") (pin "6") (pinfunction "CLK_6") (pintype "unspecified"))
      (node (ref "STM32F103CBT6") (pin "26") (pinfunction "PB13_26") (pintype "unspecified"))
    )
    (net (code "45") (name "SYS_JTCK-SWCLK") (class "Default")
      (node (ref "STLink1") (pin "3") (pinfunction "3_3") (pintype "unspecified"))
      (node (ref "STM32F103CBT6") (pin "37") (pinfunction "PA14_37") (pintype "unspecified"))
    )
    (net (code "46") (name "SYS_JTMS-SWDIO") (class "Default")
      (node (ref "STLink1") (pin "4") (pinfunction "4_4") (pintype "unspecified"))
      (node (ref "STM32F103CBT6") (pin "34") (pinfunction "PA13_34") (pintype "unspecified"))
    )
    (net (code "47") (name "USART1_RX") (class "Default")
      (node (ref "HC051") (pin "5") (pinfunction "5_5") (pintype "unspecified"))
      (node (ref "STM32F103CBT6") (pin "31") (pinfunction "PA10_31") (pintype "unspecified"))
    )
    (net (code "48") (name "USART1_TX") (class "Default")
      (node (ref "HC051") (pin "4") (pinfunction "4_4") (pintype "unspecified"))
      (node (ref "STM32F103CBT6") (pin "30") (pinfunction "PA9_30") (pintype "unspecified"))
    )
    (net (code "49") (name "USART3_RX") (class "Default")
      (node (ref "HC052") (pin "4") (pinfunction "4_4") (pintype "unspecified"))
      (node (ref "STM32F103CBT6") (pin "22") (pinfunction "PB11_22") (pintype "unspecified"))
    )
    (net (code "50") (name "USART3_TX") (class "Default")
      (node (ref "HC052") (pin "5") (pinfunction "5_5") (pintype "unspecified"))
      (node (ref "STM32F103CBT6") (pin "21") (pinfunction "PB10_21") (pintype "unspecified"))
    )
    (net (code "51") (name "VBAT_E") (class "Default")
      (node (ref "C1") (pin "2") (pinfunction "2_2") (pintype "unspecified"))
      (node (ref "STM32F103CBT6") (pin "1") (pinfunction "VBAT_1") (pintype "unspecified"))
    )
    (net (code "52") (name "VCC_USB") (class "Default")
      (node (ref "C14") (pin "2") (pinfunction "2_2") (pintype "unspecified"))
      (node (ref "D1") (pin "1") (pinfunction "A_1") (pintype "unspecified"))
      (node (ref "LED3") (pin "2") (pinfunction "A_2") (pintype "input"))
      (node (ref "LED4") (pin "2") (pinfunction "A_2") (pintype "input"))
      (node (ref "Q2") (pin "1") (pinfunction "G_1") (pintype "unspecified"))
      (node (ref "R13") (pin "2") (pinfunction "2_2") (pintype "input"))
      (node (ref "TP4056") (pin "4") (pinfunction "VCC_4") (pintype "unspecified"))
      (node (ref "TP4056") (pin "8") (pinfunction "CE_8") (pintype "unspecified"))
      (node (ref "USB1") (pin "11") (pinfunction "VBUS_11") (pintype "unspecified"))
      (node (ref "USB1") (pin "2") (pinfunction "VBUS_2") (pintype "unspecified"))
    )
    (net (code "53") (name "W25Q16_CHIP_SELECT") (class "Default")
      (node (ref "FLASH1") (pin "1") (pinfunction "/CS_1") (pintype "unspecified"))
      (node (ref "STM32F103CBT6") (pin "25") (pinfunction "PB12_25") (pintype "unspecified"))
    )
    (net (code "54") (name "unconnected-(FLASH1-IO2-Pad3)") (class "Default")
      (node (ref "FLASH1") (pin "3") (pinfunction "IO2_3") (pintype "unspecified+no_connect"))
    )
    (net (code "55") (name "unconnected-(FLASH1-IO3-Pad7)") (class "Default")
      (node (ref "FLASH1") (pin "7") (pinfunction "IO3_7") (pintype "unspecified+no_connect"))
    )
    (net (code "56") (name "unconnected-(HC051-Pad1)") (class "Default")
      (node (ref "HC051") (pin "1") (pinfunction "1_1") (pintype "unspecified+no_connect"))
    )
    (net (code "57") (name "unconnected-(HC051-Pad6)") (class "Default")
      (node (ref "HC051") (pin "6") (pinfunction "6_6") (pintype "unspecified+no_connect"))
    )
    (net (code "58") (name "unconnected-(HC052-Pad1)") (class "Default")
      (node (ref "HC052") (pin "1") (pinfunction "1_1") (pintype "unspecified+no_connect"))
    )
    (net (code "59") (name "unconnected-(HC052-Pad6)") (class "Default")
      (node (ref "HC052") (pin "6") (pinfunction "6_6") (pintype "unspecified+no_connect"))
    )
    (net (code "60") (name "unconnected-(MPU6050-AUX_CL-Pad7)") (class "Default")
      (node (ref "MPU6050") (pin "7") (pinfunction "AUX_CL_7") (pintype "unspecified+no_connect"))
    )
    (net (code "61") (name "unconnected-(MPU6050-AUX_DA-Pad6)") (class "Default")
      (node (ref "MPU6050") (pin "6") (pinfunction "AUX_DA_6") (pintype "unspecified+no_connect"))
    )
    (net (code "62") (name "unconnected-(MPU6050-EP-Pad25)") (class "Default")
      (node (ref "MPU6050") (pin "25") (pinfunction "EP_25") (pintype "unspecified+no_connect"))
    )
    (net (code "63") (name "unconnected-(MPU6050-NC-Pad2)") (class "Default")
      (node (ref "MPU6050") (pin "2") (pinfunction "NC_2") (pintype "unspecified+no_connect"))
    )
    (net (code "64") (name "unconnected-(MPU6050-NC-Pad3)") (class "Default")
      (node (ref "MPU6050") (pin "3") (pinfunction "NC_3") (pintype "unspecified+no_connect"))
    )
    (net (code "65") (name "unconnected-(MPU6050-NC-Pad4)") (class "Default")
      (node (ref "MPU6050") (pin "4") (pinfunction "NC_4") (pintype "unspecified+no_connect"))
    )
    (net (code "66") (name "unconnected-(MPU6050-NC-Pad5)") (class "Default")
      (node (ref "MPU6050") (pin "5") (pinfunction "NC_5") (pintype "unspecified+no_connect"))
    )
    (net (code "67") (name "unconnected-(MPU6050-NC-Pad14)") (class "Default")
      (node (ref "MPU6050") (pin "14") (pinfunction "NC_14") (pintype "unspecified+no_connect"))
    )
    (net (code "68") (name "unconnected-(MPU6050-NC-Pad15)") (class "Default")
      (node (ref "MPU6050") (pin "15") (pinfunction "NC_15") (pintype "unspecified+no_connect"))
    )
    (net (code "69") (name "unconnected-(MPU6050-NC-Pad16)") (class "Default")
      (node (ref "MPU6050") (pin "16") (pinfunction "NC_16") (pintype "unspecified+no_connect"))
    )
    (net (code "70") (name "unconnected-(MPU6050-NC-Pad17)") (class "Default")
      (node (ref "MPU6050") (pin "17") (pinfunction "NC_17") (pintype "unspecified+no_connect"))
    )
    (net (code "71") (name "unconnected-(MPU6050-RESV-Pad19)") (class "Default")
      (node (ref "MPU6050") (pin "19") (pinfunction "RESV_19") (pintype "unspecified+no_connect"))
    )
    (net (code "72") (name "unconnected-(MPU6050-RESV-Pad21)") (class "Default")
      (node (ref "MPU6050") (pin "21") (pinfunction "RESV_21") (pintype "unspecified+no_connect"))
    )
    (net (code "73") (name "unconnected-(MPU6050-RESV-Pad22)") (class "Default")
      (node (ref "MPU6050") (pin "22") (pinfunction "RESV_22") (pintype "unspecified+no_connect"))
    )
    (net (code "74") (name "unconnected-(RT9013-NC-Pad4)") (class "Default")
      (node (ref "RT9013") (pin "4") (pinfunction "NC_4") (pintype "unspecified+no_connect"))
    )
    (net (code "75") (name "unconnected-(STM32F103CBT6-PA4-Pad14)") (class "Default")
      (node (ref "STM32F103CBT6") (pin "14") (pinfunction "PA4_14") (pintype "unspecified+no_connect"))
    )
    (net (code "76") (name "unconnected-(STM32F103CBT6-PA5-Pad15)") (class "Default")
      (node (ref "STM32F103CBT6") (pin "15") (pinfunction "PA5_15") (pintype "unspecified+no_connect"))
    )
    (net (code "77") (name "unconnected-(STM32F103CBT6-PA6-Pad16)") (class "Default")
      (node (ref "STM32F103CBT6") (pin "16") (pinfunction "PA6_16") (pintype "unspecified+no_connect"))
    )
    (net (code "78") (name "unconnected-(STM32F103CBT6-PA7-Pad17)") (class "Default")
      (node (ref "STM32F103CBT6") (pin "17") (pinfunction "PA7_17") (pintype "unspecified+no_connect"))
    )
    (net (code "79") (name "unconnected-(STM32F103CBT6-PA11-Pad32)") (class "Default")
      (node (ref "STM32F103CBT6") (pin "32") (pinfunction "PA11_32") (pintype "unspecified+no_connect"))
    )
    (net (code "80") (name "unconnected-(STM32F103CBT6-PA12-Pad33)") (class "Default")
      (node (ref "STM32F103CBT6") (pin "33") (pinfunction "PA12_33") (pintype "unspecified+no_connect"))
    )
    (net (code "81") (name "unconnected-(STM32F103CBT6-PA15-Pad38)") (class "Default")
      (node (ref "STM32F103CBT6") (pin "38") (pinfunction "PA15_38") (pintype "unspecified+no_connect"))
    )
    (net (code "82") (name "unconnected-(STM32F103CBT6-PB2-Pad20)") (class "Default")
      (node (ref "STM32F103CBT6") (pin "20") (pinfunction "PB2_20") (pintype "unspecified+no_connect"))
    )
    (net (code "83") (name "unconnected-(STM32F103CBT6-PB3-Pad39)") (class "Default")
      (node (ref "STM32F103CBT6") (pin "39") (pinfunction "PB3_39") (pintype "unspecified+no_connect"))
    )
    (net (code "84") (name "unconnected-(STM32F103CBT6-PB5-Pad41)") (class "Default")
      (node (ref "STM32F103CBT6") (pin "41") (pinfunction "PB5_41") (pintype "unspecified+no_connect"))
    )
    (net (code "85") (name "unconnected-(STM32F103CBT6-PB6-Pad42)") (class "Default")
      (node (ref "STM32F103CBT6") (pin "42") (pinfunction "PB6_42") (pintype "unspecified+no_connect"))
    )
    (net (code "86") (name "unconnected-(STM32F103CBT6-PB7-Pad43)") (class "Default")
      (node (ref "STM32F103CBT6") (pin "43") (pinfunction "PB7_43") (pintype "unspecified+no_connect"))
    )
    (net (code "87") (name "unconnected-(STM32F103CBT6-PC13-TAMPER-RTC-Pad2)") (class "Default")
      (node (ref "STM32F103CBT6") (pin "2") (pinfunction "PC13-TAMPER-RTC_2") (pintype "unspecified+no_connect"))
    )
    (net (code "88") (name "unconnected-(STM32F103CBT6-PC14-OSC32_IN-Pad3)") (class "Default")
      (node (ref "STM32F103CBT6") (pin "3") (pinfunction "PC14-OSC32_IN_3") (pintype "unspecified+no_connect"))
    )
    (net (code "89") (name "unconnected-(STM32F103CBT6-PC15-OSC32_OUT-Pad4)") (class "Default")
      (node (ref "STM32F103CBT6") (pin "4") (pinfunction "PC15-OSC32_OUT_4") (pintype "unspecified+no_connect"))
    )
    (net (code "90") (name "unconnected-(SW1-Pad3)") (class "Default")
      (node (ref "SW1") (pin "3") (pinfunction "3_3") (pintype "unspecified+no_connect"))
    )
    (net (code "91") (name "unconnected-(SW2-Pad3)") (class "Default")
      (node (ref "SW2") (pin "3") (pinfunction "3_3") (pintype "unspecified+no_connect"))
    )
    (net (code "92") (name "unconnected-(USB1-DN1-Pad7)") (class "Default")
      (node (ref "USB1") (pin "7") (pinfunction "DN1_7") (pintype "unspecified+no_connect"))
    )
    (net (code "93") (name "unconnected-(USB1-DN2-Pad5)") (class "Default")
      (node (ref "USB1") (pin "5") (pinfunction "DN2_5") (pintype "unspecified+no_connect"))
    )
    (net (code "94") (name "unconnected-(USB1-DP1-Pad6)") (class "Default")
      (node (ref "USB1") (pin "6") (pinfunction "DP1_6") (pintype "unspecified+no_connect"))
    )
    (net (code "95") (name "unconnected-(USB1-DP2-Pad8)") (class "Default")
      (node (ref "USB1") (pin "8") (pinfunction "DP2_8") (pintype "unspecified+no_connect"))
    )
    (net (code "96") (name "unconnected-(USB1-SBU1-Pad9)") (class "Default")
      (node (ref "USB1") (pin "9") (pinfunction "SBU1_9") (pintype "unspecified+no_connect"))
    )
    (net (code "97") (name "unconnected-(USB1-SBU2-Pad3)") (class "Default")
      (node (ref "USB1") (pin "3") (pinfunction "SBU2_3") (pintype "unspecified+no_connect"))
    )
  )
)
